# EthIO_02A_MCU_Core.net
KiCad netlist of a schematic drawn in Altium Designer
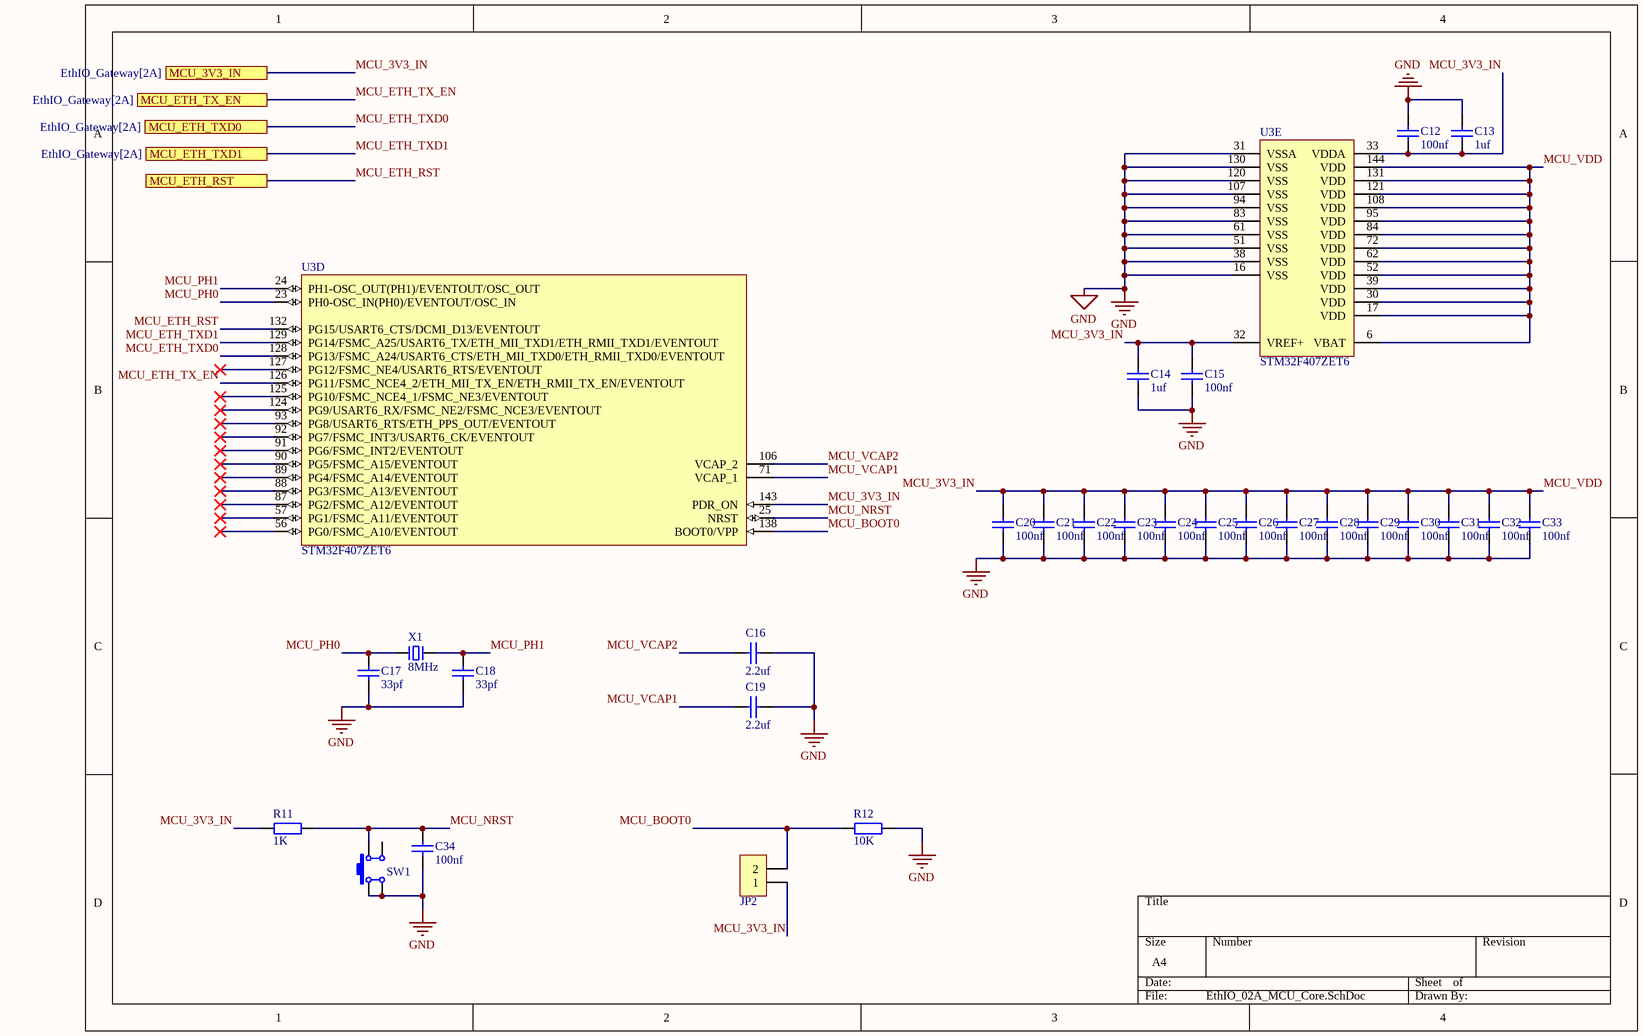
[diagram p0: EthIO_02A_MCU_Core.SchDoc]

(export (version "E")
  (design (tool "Eeschema 10.0.6"))
  (components
    (comp (ref "C12")
      (value "100nf")
      (footprint "C0805_L")
      (description "贴片电容/MLCC电容")
      (libsource (lib "0.1 - 电阻-电容-电感-保险丝-晶振-晶体-磁珠-电位器-法拉电容-馈通电容") (part "C"))
    )
    (comp (ref "C13")
      (value "1uf")
      (footprint "C0805_L")
      (description "贴片电容/MLCC电容")
      (libsource (lib "0.1 - 电阻-电容-电感-保险丝-晶振-晶体-磁珠-电位器-法拉电容-馈通电容") (part "C"))
    )
    (comp (ref "C14")
      (value "1uf")
      (footprint "C0805_L")
      (description "贴片电容/MLCC电容")
      (libsource (lib "0.1 - 电阻-电容-电感-保险丝-晶振-晶体-磁珠-电位器-法拉电容-馈通电容") (part "C"))
    )
    (comp (ref "C15")
      (value "100nf")
      (footprint "C0805_L")
      (description "贴片电容/MLCC电容")
      (libsource (lib "0.1 - 电阻-电容-电感-保险丝-晶振-晶体-磁珠-电位器-法拉电容-馈通电容") (part "C"))
    )
    (comp (ref "C16")
      (value "2.2uf")
      (footprint "C0805_L")
      (description "贴片电容/MLCC电容")
      (libsource (lib "0.1 - 电阻-电容-电感-保险丝-晶振-晶体-磁珠-电位器-法拉电容-馈通电容") (part "C"))
    )
    (comp (ref "C17")
      (value "33pf")
      (footprint "C0805_L")
      (description "贴片电容/MLCC电容")
      (libsource (lib "0.1 - 电阻-电容-电感-保险丝-晶振-晶体-磁珠-电位器-法拉电容-馈通电容") (part "C"))
    )
    (comp (ref "C18")
      (value "33pf")
      (footprint "C0805_L")
      (description "贴片电容/MLCC电容")
      (libsource (lib "0.1 - 电阻-电容-电感-保险丝-晶振-晶体-磁珠-电位器-法拉电容-馈通电容") (part "C"))
    )
    (comp (ref "C19")
      (value "2.2uf")
      (footprint "C0805_L")
      (description "贴片电容/MLCC电容")
      (libsource (lib "0.1 - 电阻-电容-电感-保险丝-晶振-晶体-磁珠-电位器-法拉电容-馈通电容") (part "C"))
    )
    (comp (ref "C20")
      (value "100nf")
      (footprint "C0805_L")
      (description "贴片电容/MLCC电容")
      (libsource (lib "0.1 - 电阻-电容-电感-保险丝-晶振-晶体-磁珠-电位器-法拉电容-馈通电容") (part "C"))
    )
    (comp (ref "C21")
      (value "100nf")
      (footprint "C0805_L")
      (description "贴片电容/MLCC电容")
      (libsource (lib "0.1 - 电阻-电容-电感-保险丝-晶振-晶体-磁珠-电位器-法拉电容-馈通电容") (part "C"))
    )
    (comp (ref "C22")
      (value "100nf")
      (footprint "C0805_L")
      (description "贴片电容/MLCC电容")
      (libsource (lib "0.1 - 电阻-电容-电感-保险丝-晶振-晶体-磁珠-电位器-法拉电容-馈通电容") (part "C"))
    )
    (comp (ref "C23")
      (value "100nf")
      (footprint "C0805_L")
      (description "贴片电容/MLCC电容")
      (libsource (lib "0.1 - 电阻-电容-电感-保险丝-晶振-晶体-磁珠-电位器-法拉电容-馈通电容") (part "C"))
    )
    (comp (ref "C24")
      (value "100nf")
      (footprint "C0805_L")
      (description "贴片电容/MLCC电容")
      (libsource (lib "0.1 - 电阻-电容-电感-保险丝-晶振-晶体-磁珠-电位器-法拉电容-馈通电容") (part "C"))
    )
    (comp (ref "C25")
      (value "100nf")
      (footprint "C0805_L")
      (description "贴片电容/MLCC电容")
      (libsource (lib "0.1 - 电阻-电容-电感-保险丝-晶振-晶体-磁珠-电位器-法拉电容-馈通电容") (part "C"))
    )
    (comp (ref "C26")
      (value "100nf")
      (footprint "C0805_L")
      (description "贴片电容/MLCC电容")
      (libsource (lib "0.1 - 电阻-电容-电感-保险丝-晶振-晶体-磁珠-电位器-法拉电容-馈通电容") (part "C"))
    )
    (comp (ref "C27")
      (value "100nf")
      (footprint "C0805_L")
      (description "贴片电容/MLCC电容")
      (libsource (lib "0.1 - 电阻-电容-电感-保险丝-晶振-晶体-磁珠-电位器-法拉电容-馈通电容") (part "C"))
    )
    (comp (ref "C28")
      (value "100nf")
      (footprint "C0805_L")
      (description "贴片电容/MLCC电容")
      (libsource (lib "0.1 - 电阻-电容-电感-保险丝-晶振-晶体-磁珠-电位器-法拉电容-馈通电容") (part "C"))
    )
    (comp (ref "C29")
      (value "100nf")
      (footprint "C0805_L")
      (description "贴片电容/MLCC电容")
      (libsource (lib "0.1 - 电阻-电容-电感-保险丝-晶振-晶体-磁珠-电位器-法拉电容-馈通电容") (part "C"))
    )
    (comp (ref "C30")
      (value "100nf")
      (footprint "C0805_L")
      (description "贴片电容/MLCC电容")
      (libsource (lib "0.1 - 电阻-电容-电感-保险丝-晶振-晶体-磁珠-电位器-法拉电容-馈通电容") (part "C"))
    )
    (comp (ref "C31")
      (value "100nf")
      (footprint "C0805_L")
      (description "贴片电容/MLCC电容")
      (libsource (lib "0.1 - 电阻-电容-电感-保险丝-晶振-晶体-磁珠-电位器-法拉电容-馈通电容") (part "C"))
    )
    (comp (ref "C32")
      (value "100nf")
      (footprint "C0805_L")
      (description "贴片电容/MLCC电容")
      (libsource (lib "0.1 - 电阻-电容-电感-保险丝-晶振-晶体-磁珠-电位器-法拉电容-馈通电容") (part "C"))
    )
    (comp (ref "C33")
      (value "100nf")
      (footprint "C0805_L")
      (description "贴片电容/MLCC电容")
      (libsource (lib "0.1 - 电阻-电容-电感-保险丝-晶振-晶体-磁珠-电位器-法拉电容-馈通电容") (part "C"))
    )
    (comp (ref "C34")
      (value "100nf")
      (footprint "C0805_L")
      (description "贴片电容/MLCC电容")
      (libsource (lib "0.1 - 电阻-电容-电感-保险丝-晶振-晶体-磁珠-电位器-法拉电容-馈通电容") (part "C"))
    )
    (comp (ref "JP2")
      (value "HDR-1X2")
      (footprint "XH2.54-LI-2P")
      (description "跳帽")
      (libsource (lib "5.5 - 2.54mm连接器(KF2EDGK_XH2.54_2.54排针排母)") (part "Header 2"))
    )
    (comp (ref "R11")
      (value "1K")
      (footprint "R0805_L")
      (description "贴片电阻")
      (libsource (lib "0.1 - 电阻-电容-电感-保险丝-晶振-晶体-磁珠-电位器-法拉电容-馈通电容") (part "R"))
    )
    (comp (ref "R12")
      (value "10K")
      (footprint "R0805_L")
      (description "贴片电阻")
      (libsource (lib "0.1 - 电阻-电容-电感-保险丝-晶振-晶体-磁珠-电位器-法拉电容-馈通电容") (part "R"))
    )
    (comp (ref "SW1")
      (value "12x12x5")
      (footprint "SW DIP-12*12*4.3")
      (description "直插12x12轻触开关")
      (libsource (lib "0.5 - 按键_开关_蜂鸣器_电池_测试点_Mark点_铜柱") (part "SW DIP-12x12"))
    )
    (comp (ref "U3")
      (value "STM32F407ZET6")
      (footprint "TQFP144_V")
      (libsource (lib "2.7 - STM32 F4系列单片机") (part "STM32F407ZET6"))
    )
    (comp (ref "X1")
      (value "8MHz")
      (footprint "HC-49S")
      (description "2脚无源晶振(谐振器）")
      (libsource (lib "0.1 - 电阻-电容-电感-保险丝-晶振-晶体-磁珠-电位器-法拉电容-馈通电容") (part "XTAL-2P"))
    )
  )
  (nets
    (net (code "1") (name "/MCU_3V3_IN") (class "Default")
      (node (ref "C12") (pin "1") (pinfunction "1_1") (pintype "passive"))
      (node (ref "C13") (pin "1") (pinfunction "1_1") (pintype "passive"))
      (node (ref "C14") (pin "1") (pinfunction "1_1") (pintype "passive"))
      (node (ref "C15") (pin "1") (pinfunction "1_1") (pintype "passive"))
      (node (ref "C20") (pin "1") (pinfunction "1_1") (pintype "passive"))
      (node (ref "C21") (pin "1") (pinfunction "1_1") (pintype "passive"))
      (node (ref "C22") (pin "1") (pinfunction "1_1") (pintype "passive"))
      (node (ref "C23") (pin "1") (pinfunction "1_1") (pintype "passive"))
      (node (ref "C24") (pin "1") (pinfunction "1_1") (pintype "passive"))
      (node (ref "C25") (pin "1") (pinfunction "1_1") (pintype "passive"))
      (node (ref "C26") (pin "1") (pinfunction "1_1") (pintype "passive"))
      (node (ref "C27") (pin "1") (pinfunction "1_1") (pintype "passive"))
      (node (ref "C28") (pin "1") (pinfunction "1_1") (pintype "passive"))
      (node (ref "C29") (pin "1") (pinfunction "1_1") (pintype "passive"))
      (node (ref "C30") (pin "1") (pinfunction "1_1") (pintype "passive"))
      (node (ref "C31") (pin "1") (pinfunction "1_1") (pintype "passive"))
      (node (ref "C32") (pin "1") (pinfunction "1_1") (pintype "passive"))
      (node (ref "C33") (pin "1") (pinfunction "1_1") (pintype "passive"))
      (node (ref "JP2") (pin "1") (pinfunction "1_1") (pintype "passive"))
      (node (ref "R11") (pin "1") (pinfunction "1_1") (pintype "passive"))
      (node (ref "U3") (pin "108") (pinfunction "VDD_108") (pintype "power_in"))
      (node (ref "U3") (pin "121") (pinfunction "VDD_121") (pintype "power_in"))
      (node (ref "U3") (pin "131") (pinfunction "VDD_131") (pintype "power_in"))
      (node (ref "U3") (pin "143") (pinfunction "PDR_ON_143") (pintype "input"))
      (node (ref "U3") (pin "144") (pinfunction "VDD_144") (pintype "power_in"))
      (node (ref "U3") (pin "17") (pinfunction "VDD_17") (pintype "power_in"))
      (node (ref "U3") (pin "30") (pinfunction "VDD_30") (pintype "power_in"))
      (node (ref "U3") (pin "32") (pinfunction "VREF+_32") (pintype "power_in"))
      (node (ref "U3") (pin "33") (pinfunction "VDDA_33") (pintype "power_in"))
      (node (ref "U3") (pin "39") (pinfunction "VDD_39") (pintype "power_in"))
      (node (ref "U3") (pin "52") (pinfunction "VDD_52") (pintype "power_in"))
      (node (ref "U3") (pin "6") (pinfunction "VBAT_6") (pintype "power_in"))
      (node (ref "U3") (pin "62") (pinfunction "VDD_62") (pintype "power_in"))
      (node (ref "U3") (pin "72") (pinfunction "VDD_72") (pintype "power_in"))
      (node (ref "U3") (pin "84") (pinfunction "VDD_84") (pintype "power_in"))
      (node (ref "U3") (pin "95") (pinfunction "VDD_95") (pintype "power_in"))
    )
    (net (code "2") (name "/MCU_BOOT0") (class "Default")
      (node (ref "JP2") (pin "2") (pinfunction "2_2") (pintype "passive"))
      (node (ref "R12") (pin "1") (pinfunction "1_1") (pintype "passive"))
      (node (ref "U3") (pin "138") (pinfunction "BOOT0/VPP_138") (pintype "input"))
    )
    (net (code "3") (name "/MCU_ETH_RST") (class "Default")
      (node (ref "U3") (pin "132") (pinfunction "PG15/USART6_CTS/DCMI_D13/EVENTOUT_132") (pintype "bidirectional"))
    )
    (net (code "4") (name "/MCU_ETH_TXD0") (class "Default")
      (node (ref "U3") (pin "128") (pinfunction "PG13/FSMC_A24/USART6_CTS/ETH_MII_TXD0/ETH_RMII_TXD0/EVENTOUT_128") (pintype "bidirectional"))
    )
    (net (code "5") (name "/MCU_ETH_TXD1") (class "Default")
      (node (ref "U3") (pin "129") (pinfunction "PG14/FSMC_A25/USART6_TX/ETH_MII_TXD1/ETH_RMII_TXD1/EVENTOUT_129") (pintype "bidirectional"))
    )
    (net (code "6") (name "/MCU_ETH_TX_EN") (class "Default")
      (node (ref "U3") (pin "126") (pinfunction "PG11/FSMC_NCE4_2/ETH_MII_TX_EN/ETH_RMII_TX_EN/EVENTOUT_126") (pintype "bidirectional"))
    )
    (net (code "7") (name "/MCU_NRST") (class "Default")
      (node (ref "C34") (pin "1") (pinfunction "1_1") (pintype "passive"))
      (node (ref "R11") (pin "2") (pinfunction "2_2") (pintype "passive"))
      (node (ref "SW1") (pin "2") (pinfunction "2_2") (pintype "passive"))
      (node (ref "U3") (pin "25") (pinfunction "NRST_25") (pintype "bidirectional"))
    )
    (net (code "8") (name "/MCU_PH0") (class "Default")
      (node (ref "C17") (pin "1") (pinfunction "1_1") (pintype "passive"))
      (node (ref "U3") (pin "23") (pinfunction "PH0-OSC_IN(PH0)/EVENTOUT/OSC_IN_23") (pintype "bidirectional"))
      (node (ref "X1") (pin "1") (pinfunction "1_1") (pintype "passive"))
    )
    (net (code "9") (name "/MCU_PH1") (class "Default")
      (node (ref "C18") (pin "1") (pinfunction "1_1") (pintype "passive"))
      (node (ref "U3") (pin "24") (pinfunction "PH1-OSC_OUT(PH1)/EVENTOUT/OSC_OUT_24") (pintype "bidirectional"))
      (node (ref "X1") (pin "2") (pinfunction "2_2") (pintype "passive"))
    )
    (net (code "10") (name "/MCU_VCAP1") (class "Default")
      (node (ref "C19") (pin "1") (pinfunction "1_1") (pintype "passive"))
      (node (ref "U3") (pin "71") (pinfunction "VCAP_1_71") (pintype "power_in"))
    )
    (net (code "11") (name "/MCU_VCAP2") (class "Default")
      (node (ref "C16") (pin "1") (pinfunction "1_1") (pintype "passive"))
      (node (ref "U3") (pin "106") (pinfunction "VCAP_2_106") (pintype "power_in"))
    )
    (net (code "12") (name "GND") (class "Default")
      (node (ref "C12") (pin "2") (pinfunction "2_2") (pintype "passive"))
      (node (ref "C13") (pin "2") (pinfunction "2_2") (pintype "passive"))
      (node (ref "C14") (pin "2") (pinfunction "2_2") (pintype "passive"))
      (node (ref "C15") (pin "2") (pinfunction "2_2") (pintype "passive"))
      (node (ref "C16") (pin "2") (pinfunction "2_2") (pintype "passive"))
      (node (ref "C17") (pin "2") (pinfunction "2_2") (pintype "passive"))
      (node (ref "C18") (pin "2") (pinfunction "2_2") (pintype "passive"))
      (node (ref "C19") (pin "2") (pinfunction "2_2") (pintype "passive"))
      (node (ref "C20") (pin "2") (pinfunction "2_2") (pintype "passive"))
      (node (ref "C21") (pin "2") (pinfunction "2_2") (pintype "passive"))
      (node (ref "C22") (pin "2") (pinfunction "2_2") (pintype "passive"))
      (node (ref "C23") (pin "2") (pinfunction "2_2") (pintype "passive"))
      (node (ref "C24") (pin "2") (pinfunction "2_2") (pintype "passive"))
      (node (ref "C25") (pin "2") (pinfunction "2_2") (pintype "passive"))
      (node (ref "C26") (pin "2") (pinfunction "2_2") (pintype "passive"))
      (node (ref "C27") (pin "2") (pinfunction "2_2") (pintype "passive"))
      (node (ref "C28") (pin "2") (pinfunction "2_2") (pintype "passive"))
      (node (ref "C29") (pin "2") (pinfunction "2_2") (pintype "passive"))
      (node (ref "C30") (pin "2") (pinfunction "2_2") (pintype "passive"))
      (node (ref "C31") (pin "2") (pinfunction "2_2") (pintype "passive"))
      (node (ref "C32") (pin "2") (pinfunction "2_2") (pintype "passive"))
      (node (ref "C33") (pin "2") (pinfunction "2_2") (pintype "passive"))
      (node (ref "C34") (pin "2") (pinfunction "2_2") (pintype "passive"))
      (node (ref "R12") (pin "2") (pinfunction "2_2") (pintype "passive"))
      (node (ref "SW1") (pin "1") (pinfunction "1_1") (pintype "passive"))
      (node (ref "SW1") (pin "4") (pinfunction "4_4") (pintype "passive"))
      (node (ref "U3") (pin "107") (pinfunction "VSS_107") (pintype "power_in"))
      (node (ref "U3") (pin "120") (pinfunction "VSS_120") (pintype "power_in"))
      (node (ref "U3") (pin "130") (pinfunction "VSS_130") (pintype "power_in"))
      (node (ref "U3") (pin "16") (pinfunction "VSS_16") (pintype "power_in"))
      (node (ref "U3") (pin "31") (pinfunction "VSSA_31") (pintype "power_in"))
      (node (ref "U3") (pin "38") (pinfunction "VSS_38") (pintype "power_in"))
      (node (ref "U3") (pin "51") (pinfunction "VSS_51") (pintype "power_in"))
      (node (ref "U3") (pin "61") (pinfunction "VSS_61") (pintype "power_in"))
      (node (ref "U3") (pin "83") (pinfunction "VSS_83") (pintype "power_in"))
      (node (ref "U3") (pin "94") (pinfunction "VSS_94") (pintype "power_in"))
    )
    (net (code "13") (name "unconnected-(SW1-Pad3)") (class "Default")
      (node (ref "SW1") (pin "3") (pinfunction "3_3") (pintype "passive"))
    )
    (net (code "14") (name "unconnected-(U3D-PG0{slash}FSMC_A10{slash}EVENTOUT-Pad56)") (class "Default")
      (node (ref "U3") (pin "56") (pinfunction "PG0/FSMC_A10/EVENTOUT_56") (pintype "bidirectional+no_connect"))
    )
    (net (code "15") (name "unconnected-(U3D-PG1{slash}FSMC_A11{slash}EVENTOUT-Pad57)") (class "Default")
      (node (ref "U3") (pin "57") (pinfunction "PG1/FSMC_A11/EVENTOUT_57") (pintype "bidirectional+no_connect"))
    )
    (net (code "16") (name "unconnected-(U3D-PG2{slash}FSMC_A12{slash}EVENTOUT-Pad87)") (class "Default")
      (node (ref "U3") (pin "87") (pinfunction "PG2/FSMC_A12/EVENTOUT_87") (pintype "bidirectional+no_connect"))
    )
    (net (code "17") (name "unconnected-(U3D-PG3{slash}FSMC_A13{slash}EVENTOUT-Pad88)") (class "Default")
      (node (ref "U3") (pin "88") (pinfunction "PG3/FSMC_A13/EVENTOUT_88") (pintype "bidirectional+no_connect"))
    )
    (net (code "18") (name "unconnected-(U3D-PG4{slash}FSMC_A14{slash}EVENTOUT-Pad89)") (class "Default")
      (node (ref "U3") (pin "89") (pinfunction "PG4/FSMC_A14/EVENTOUT_89") (pintype "bidirectional+no_connect"))
    )
    (net (code "19") (name "unconnected-(U3D-PG5{slash}FSMC_A15{slash}EVENTOUT-Pad90)") (class "Default")
      (node (ref "U3") (pin "90") (pinfunction "PG5/FSMC_A15/EVENTOUT_90") (pintype "bidirectional+no_connect"))
    )
    (net (code "20") (name "unconnected-(U3D-PG6{slash}FSMC_INT2{slash}EVENTOUT-Pad91)") (class "Default")
      (node (ref "U3") (pin "91") (pinfunction "PG6/FSMC_INT2/EVENTOUT_91") (pintype "bidirectional+no_connect"))
    )
    (net (code "21") (name "unconnected-(U3D-PG7{slash}FSMC_INT3{slash}USART6_CK{slash}EVENTOUT-Pad92)") (class "Default")
      (node (ref "U3") (pin "92") (pinfunction "PG7/FSMC_INT3/USART6_CK/EVENTOUT_92") (pintype "bidirectional+no_connect"))
    )
    (net (code "22") (name "unconnected-(U3D-PG8{slash}USART6_RTS{slash}ETH_PPS_OUT{slash}EVENTOUT-Pad93)") (class "Default")
      (node (ref "U3") (pin "93") (pinfunction "PG8/USART6_RTS/ETH_PPS_OUT/EVENTOUT_93") (pintype "bidirectional+no_connect"))
    )
    (net (code "23") (name "unconnected-(U3D-PG9{slash}USART6_RX{slash}FSMC_NE2{slash}FSMC_NCE3{slash}EVENTOUT-Pad124)") (class "Default")
      (node (ref "U3") (pin "124") (pinfunction "PG9/USART6_RX/FSMC_NE2/FSMC_NCE3/EVENTOUT_124") (pintype "bidirectional+no_connect"))
    )
    (net (code "24") (name "unconnected-(U3D-PG10{slash}FSMC_NCE4_1{slash}FSMC_NE3{slash}EVENTOUT-Pad125)") (class "Default")
      (node (ref "U3") (pin "125") (pinfunction "PG10/FSMC_NCE4_1/FSMC_NE3/EVENTOUT_125") (pintype "bidirectional+no_connect"))
    )
    (net (code "25") (name "unconnected-(U3D-PG12{slash}FSMC_NE4{slash}USART6_RTS{slash}EVENTOUT-Pad127)") (class "Default")
      (node (ref "U3") (pin "127") (pinfunction "PG12/FSMC_NE4/USART6_RTS/EVENTOUT_127") (pintype "bidirectional+no_connect"))
    )
  )
)
